# DM1097_MODULE_HSPEED.net
KiCad netlist of a schematic drawn in Altium Designer
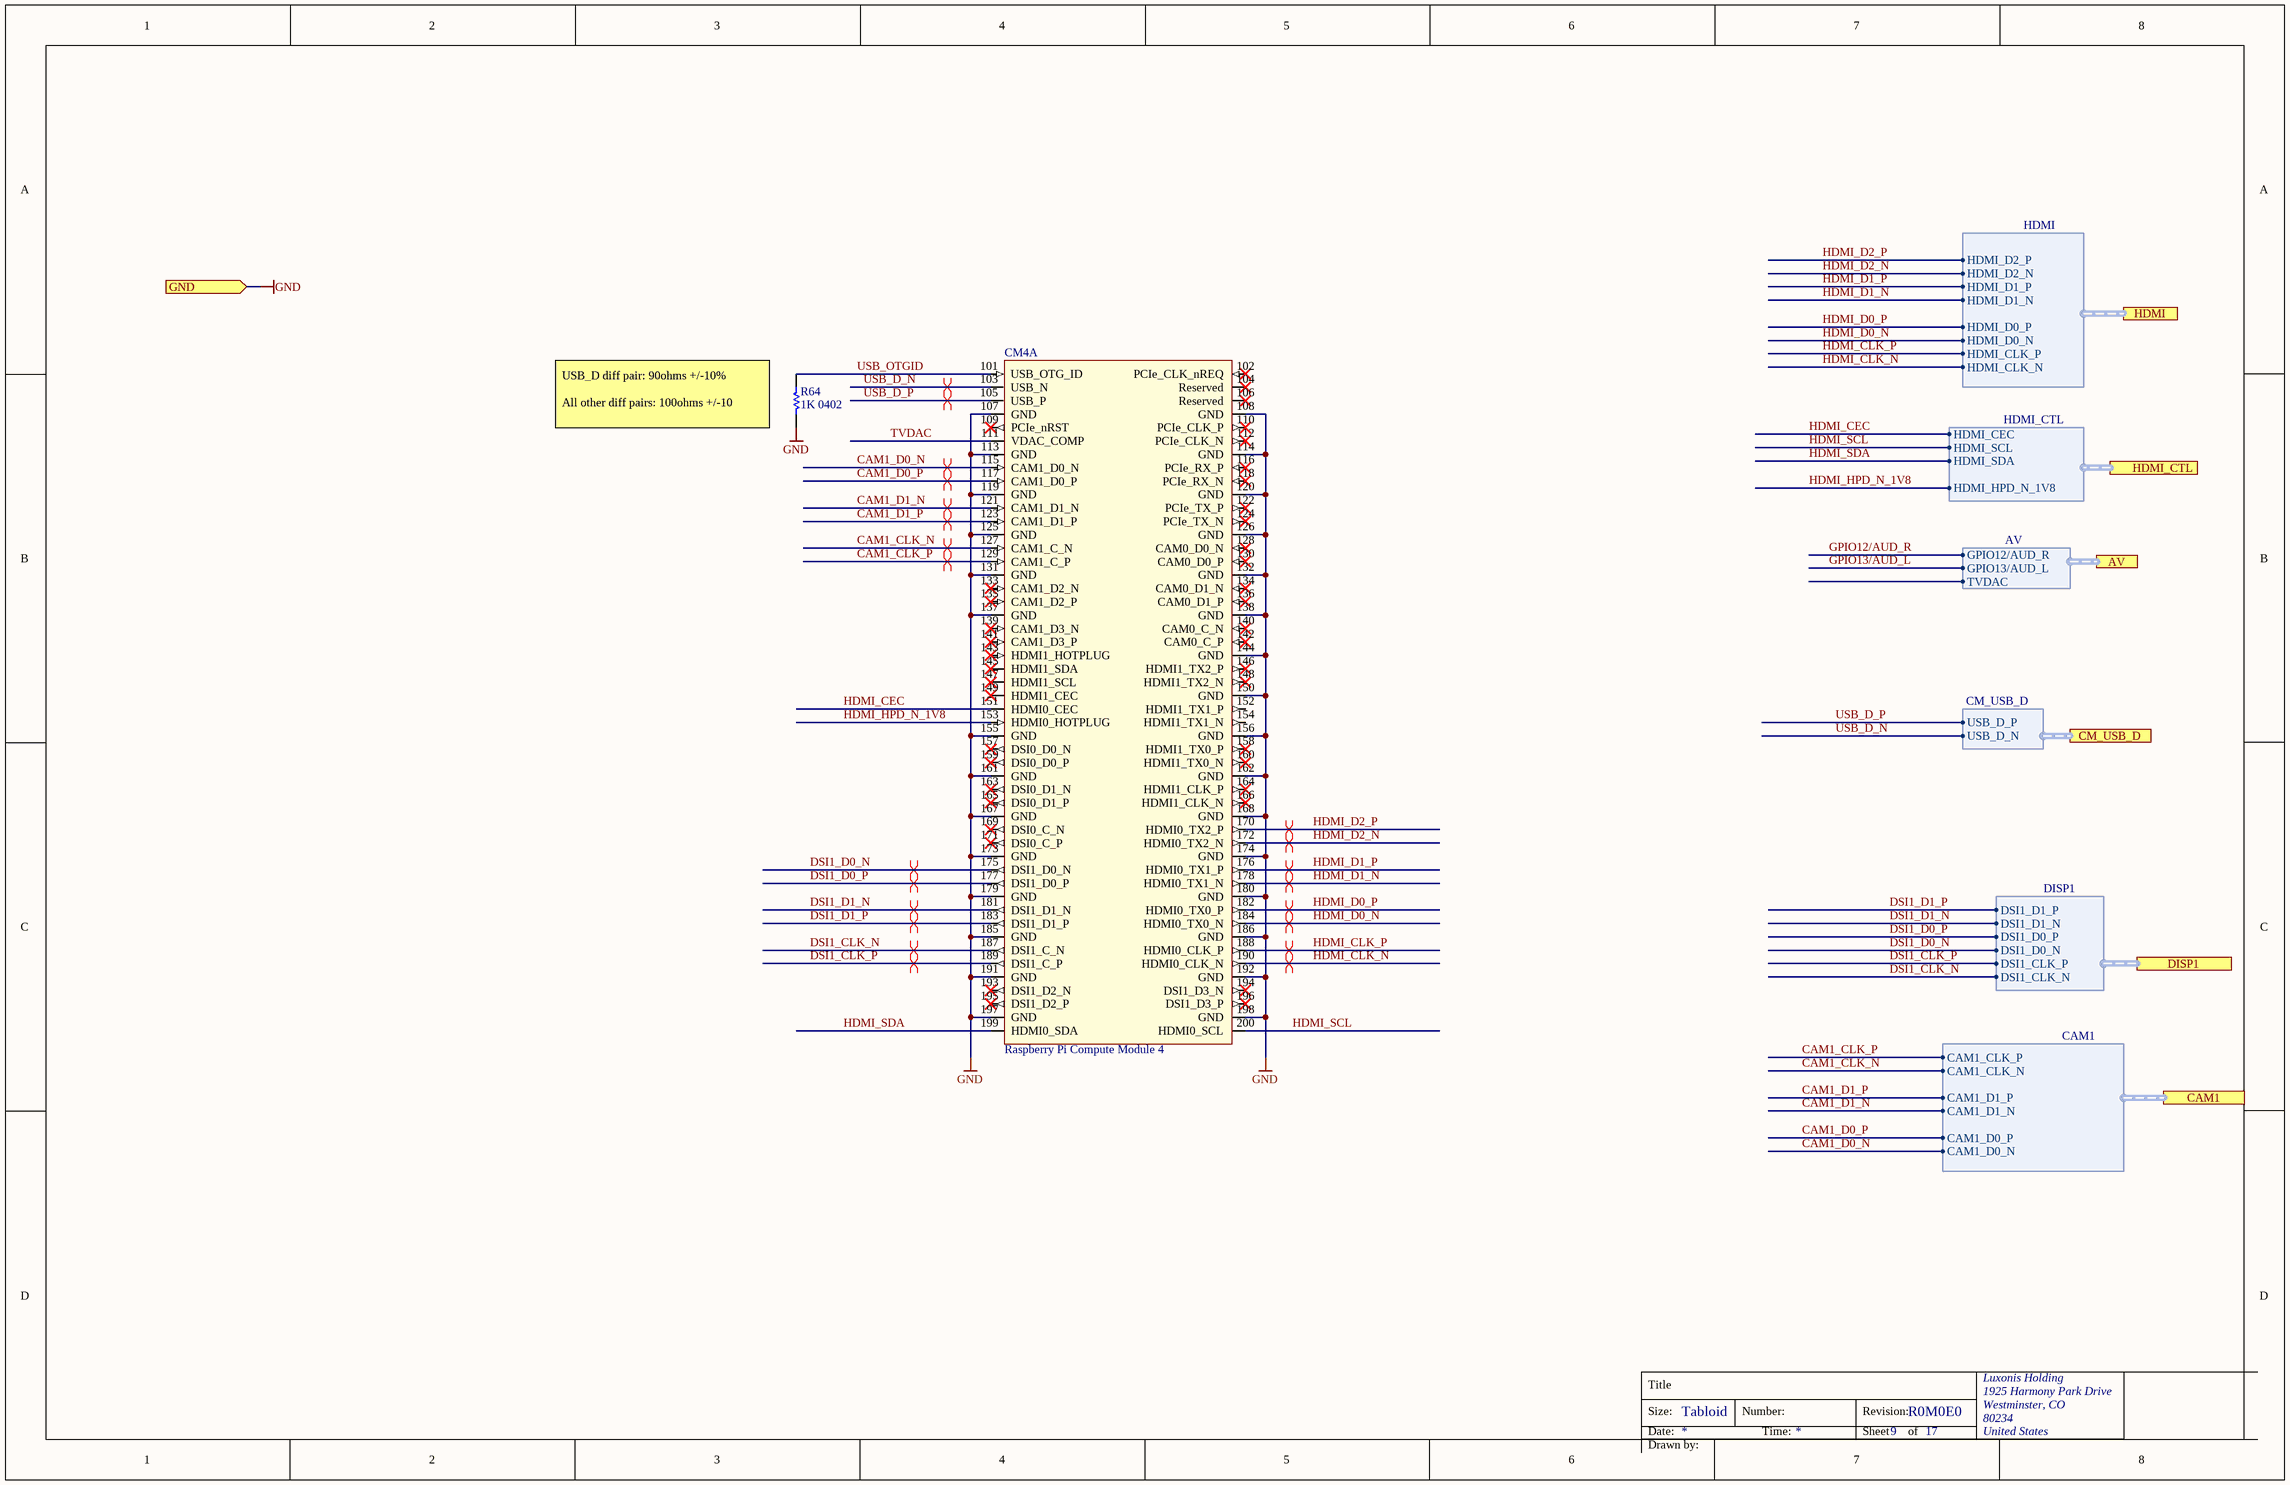
[diagram p0: DM1097_MODULE_HSPEED.SchDoc]

(export (version "E")
  (design (tool "Eeschema 10.0.6"))
  (components
    (comp (ref "CM4")
      (value "Raspberry Pi Compute Module 4")
      (footprint "CM4-DF40HC(3.0)-100DS-0.4v_3mm_1.5mm")
      (description "Raspberry Pi Compute Module 4\r\nTwo receptacle 100-pin connectors")
      (libsource (lib "DM1097_SchLib") (part "CM4"))
    )
    (comp (ref "R64")
      (value "1K 0402")
      (footprint "RES_Altium_Vault_Generic:RESC0402(1005)_N")
      (fields (field (name "TOLERANCE") "1%"))
      (libsource (lib "LuxonisMaster") (part "RC0402FR-071KL"))
    )
  )
  (nets
    (net (code "7") (name "/CAM1_CLK_N") (class "Default")
      (node (ref "CM4") (pin "127") (pinfunction "CAM1_C_N_127") (pintype "input"))
    )
    (net (code "8") (name "/CAM1_CLK_P") (class "Default")
      (node (ref "CM4") (pin "129") (pinfunction "CAM1_C_P_129") (pintype "input"))
    )
    (net (code "9") (name "/CAM1_D0_N") (class "Default")
      (node (ref "CM4") (pin "115") (pinfunction "CAM1_D0_N_115") (pintype "input"))
    )
    (net (code "10") (name "/CAM1_D0_P") (class "Default")
      (node (ref "CM4") (pin "117") (pinfunction "CAM1_D0_P_117") (pintype "input"))
    )
    (net (code "11") (name "/CAM1_D1_N") (class "Default")
      (node (ref "CM4") (pin "121") (pinfunction "CAM1_D1_N_121") (pintype "input"))
    )
    (net (code "12") (name "/CAM1_D1_P") (class "Default")
      (node (ref "CM4") (pin "123") (pinfunction "CAM1_D1_P_123") (pintype "input"))
    )
    (net (code "13") (name "/DSI1_CLK_N") (class "Default")
      (node (ref "CM4") (pin "187") (pinfunction "DSI1_C_N_187") (pintype "output"))
    )
    (net (code "14") (name "/DSI1_CLK_P") (class "Default")
      (node (ref "CM4") (pin "189") (pinfunction "DSI1_C_P_189") (pintype "output"))
    )
    (net (code "15") (name "/DSI1_D0_N") (class "Default")
      (node (ref "CM4") (pin "175") (pinfunction "DSI1_D0_N_175") (pintype "output"))
    )
    (net (code "16") (name "/DSI1_D0_P") (class "Default")
      (node (ref "CM4") (pin "177") (pinfunction "DSI1_D0_P_177") (pintype "output"))
    )
    (net (code "17") (name "/DSI1_D1_N") (class "Default")
      (node (ref "CM4") (pin "181") (pinfunction "DSI1_D1_N_181") (pintype "output"))
    )
    (net (code "18") (name "/DSI1_D1_P") (class "Default")
      (node (ref "CM4") (pin "183") (pinfunction "DSI1_D1_P_183") (pintype "output"))
    )
    (net (code "21") (name "/HDMI_CEC") (class "Default")
      (node (ref "CM4") (pin "151") (pinfunction "HDMI0_CEC_151") (pintype "open_collector"))
    )
    (net (code "22") (name "/HDMI_CLK_N") (class "Default")
      (node (ref "CM4") (pin "190") (pinfunction "HDMI0_CLK_N_190") (pintype "output"))
    )
    (net (code "23") (name "/HDMI_CLK_P") (class "Default")
      (node (ref "CM4") (pin "188") (pinfunction "HDMI0_CLK_P_188") (pintype "output"))
    )
    (net (code "24") (name "/HDMI_D0_N") (class "Default")
      (node (ref "CM4") (pin "184") (pinfunction "HDMI0_TX0_N_184") (pintype "output"))
    )
    (net (code "25") (name "/HDMI_D0_P") (class "Default")
      (node (ref "CM4") (pin "182") (pinfunction "HDMI0_TX0_P_182") (pintype "output"))
    )
    (net (code "26") (name "/HDMI_D1_N") (class "Default")
      (node (ref "CM4") (pin "178") (pinfunction "HDMI0_TX1_N_178") (pintype "output"))
    )
    (net (code "27") (name "/HDMI_D1_P") (class "Default")
      (node (ref "CM4") (pin "176") (pinfunction "HDMI0_TX1_P_176") (pintype "output"))
    )
    (net (code "28") (name "/HDMI_D2_N") (class "Default")
      (node (ref "CM4") (pin "172") (pinfunction "HDMI0_TX2_N_172") (pintype "output"))
    )
    (net (code "29") (name "/HDMI_D2_P") (class "Default")
      (node (ref "CM4") (pin "170") (pinfunction "HDMI0_TX2_P_170") (pintype "output"))
    )
    (net (code "30") (name "/HDMI_HPD_N_1V8") (class "Default")
      (node (ref "CM4") (pin "153") (pinfunction "HDMI0_HOTPLUG_153") (pintype "input"))
    )
    (net (code "31") (name "/HDMI_SCL") (class "Default")
      (node (ref "CM4") (pin "200") (pinfunction "HDMI0_SCL_200") (pintype "open_collector"))
    )
    (net (code "32") (name "/HDMI_SDA") (class "Default")
      (node (ref "CM4") (pin "199") (pinfunction "HDMI0_SDA_199") (pintype "bidirectional"))
    )
    (net (code "33") (name "/TVDAC") (class "Default")
      (node (ref "CM4") (pin "111") (pinfunction "VDAC_COMP_111") (pintype "passive"))
    )
    (net (code "34") (name "/USB_D_N") (class "Default")
      (node (ref "CM4") (pin "103") (pinfunction "USB_N_103") (pintype "passive"))
    )
    (net (code "35") (name "/USB_D_P") (class "Default")
      (node (ref "CM4") (pin "105") (pinfunction "USB_P_105") (pintype "passive"))
    )
    (net (code "36") (name "/USB_OTGID") (class "Default")
      (node (ref "CM4") (pin "101") (pinfunction "USB_OTG_ID_101") (pintype "input"))
      (node (ref "R64") (pin "2") (pinfunction "2_2") (pintype "passive"))
    )
    (net (code "43") (name "GND") (class "Default")
      (node (ref "CM4") (pin "107") (pinfunction "GND_107") (pintype "power_in"))
      (node (ref "CM4") (pin "108") (pinfunction "GND_108") (pintype "power_in"))
      (node (ref "CM4") (pin "113") (pinfunction "GND_113") (pintype "power_in"))
      (node (ref "CM4") (pin "114") (pinfunction "GND_114") (pintype "power_in"))
      (node (ref "CM4") (pin "119") (pinfunction "GND_119") (pintype "power_in"))
      (node (ref "CM4") (pin "120") (pinfunction "GND_120") (pintype "power_in"))
      (node (ref "CM4") (pin "125") (pinfunction "GND_125") (pintype "power_in"))
      (node (ref "CM4") (pin "126") (pinfunction "GND_126") (pintype "power_in"))
      (node (ref "CM4") (pin "131") (pinfunction "GND_131") (pintype "power_in"))
      (node (ref "CM4") (pin "132") (pinfunction "GND_132") (pintype "power_in"))
      (node (ref "CM4") (pin "137") (pinfunction "GND_137") (pintype "power_in"))
      (node (ref "CM4") (pin "138") (pinfunction "GND_138") (pintype "power_in"))
      (node (ref "CM4") (pin "144") (pinfunction "GND_144") (pintype "power_in"))
      (node (ref "CM4") (pin "150") (pinfunction "GND_150") (pintype "power_in"))
      (node (ref "CM4") (pin "155") (pinfunction "GND_155") (pintype "power_in"))
      (node (ref "CM4") (pin "156") (pinfunction "GND_156") (pintype "power_in"))
      (node (ref "CM4") (pin "161") (pinfunction "GND_161") (pintype "power_in"))
      (node (ref "CM4") (pin "162") (pinfunction "GND_162") (pintype "power_in"))
      (node (ref "CM4") (pin "167") (pinfunction "GND_167") (pintype "power_in"))
      (node (ref "CM4") (pin "168") (pinfunction "GND_168") (pintype "power_in"))
      (node (ref "CM4") (pin "173") (pinfunction "GND_173") (pintype "power_in"))
      (node (ref "CM4") (pin "174") (pinfunction "GND_174") (pintype "power_in"))
      (node (ref "CM4") (pin "179") (pinfunction "GND_179") (pintype "power_in"))
      (node (ref "CM4") (pin "180") (pinfunction "GND_180") (pintype "power_in"))
      (node (ref "CM4") (pin "185") (pinfunction "GND_185") (pintype "power_in"))
      (node (ref "CM4") (pin "186") (pinfunction "GND_186") (pintype "power_in"))
      (node (ref "CM4") (pin "191") (pinfunction "GND_191") (pintype "power_in"))
      (node (ref "CM4") (pin "192") (pinfunction "GND_192") (pintype "power_in"))
      (node (ref "CM4") (pin "197") (pinfunction "GND_197") (pintype "power_in"))
      (node (ref "CM4") (pin "198") (pinfunction "GND_198") (pintype "power_in"))
      (node (ref "R64") (pin "1") (pinfunction "1_1") (pintype "passive"))
    )
    (net (code "44") (name "unconnected-(CM4A-CAM0_C_N-Pad140)") (class "Default")
      (node (ref "CM4") (pin "140") (pinfunction "CAM0_C_N_140") (pintype "input+no_connect"))
    )
    (net (code "45") (name "unconnected-(CM4A-CAM0_C_P-Pad142)") (class "Default")
      (node (ref "CM4") (pin "142") (pinfunction "CAM0_C_P_142") (pintype "input+no_connect"))
    )
    (net (code "46") (name "unconnected-(CM4A-CAM0_D0_N-Pad128)") (class "Default")
      (node (ref "CM4") (pin "128") (pinfunction "CAM0_D0_N_128") (pintype "input+no_connect"))
    )
    (net (code "47") (name "unconnected-(CM4A-CAM0_D0_P-Pad130)") (class "Default")
      (node (ref "CM4") (pin "130") (pinfunction "CAM0_D0_P_130") (pintype "input+no_connect"))
    )
    (net (code "48") (name "unconnected-(CM4A-CAM0_D1_N-Pad134)") (class "Default")
      (node (ref "CM4") (pin "134") (pinfunction "CAM0_D1_N_134") (pintype "input+no_connect"))
    )
    (net (code "49") (name "unconnected-(CM4A-CAM0_D1_P-Pad136)") (class "Default")
      (node (ref "CM4") (pin "136") (pinfunction "CAM0_D1_P_136") (pintype "input+no_connect"))
    )
    (net (code "50") (name "unconnected-(CM4A-CAM1_D2_N-Pad133)") (class "Default")
      (node (ref "CM4") (pin "133") (pinfunction "CAM1_D2_N_133") (pintype "input+no_connect"))
    )
    (net (code "51") (name "unconnected-(CM4A-CAM1_D2_P-Pad135)") (class "Default")
      (node (ref "CM4") (pin "135") (pinfunction "CAM1_D2_P_135") (pintype "input+no_connect"))
    )
    (net (code "52") (name "unconnected-(CM4A-CAM1_D3_N-Pad139)") (class "Default")
      (node (ref "CM4") (pin "139") (pinfunction "CAM1_D3_N_139") (pintype "input+no_connect"))
    )
    (net (code "53") (name "unconnected-(CM4A-CAM1_D3_P-Pad141)") (class "Default")
      (node (ref "CM4") (pin "141") (pinfunction "CAM1_D3_P_141") (pintype "input+no_connect"))
    )
    (net (code "54") (name "unconnected-(CM4A-DSI0_C_N-Pad169)") (class "Default")
      (node (ref "CM4") (pin "169") (pinfunction "DSI0_C_N_169") (pintype "output+no_connect"))
    )
    (net (code "55") (name "unconnected-(CM4A-DSI0_C_P-Pad171)") (class "Default")
      (node (ref "CM4") (pin "171") (pinfunction "DSI0_C_P_171") (pintype "output+no_connect"))
    )
    (net (code "56") (name "unconnected-(CM4A-DSI0_D0_N-Pad157)") (class "Default")
      (node (ref "CM4") (pin "157") (pinfunction "DSI0_D0_N_157") (pintype "output+no_connect"))
    )
    (net (code "57") (name "unconnected-(CM4A-DSI0_D0_P-Pad159)") (class "Default")
      (node (ref "CM4") (pin "159") (pinfunction "DSI0_D0_P_159") (pintype "output+no_connect"))
    )
    (net (code "58") (name "unconnected-(CM4A-DSI0_D1_N-Pad163)") (class "Default")
      (node (ref "CM4") (pin "163") (pinfunction "DSI0_D1_N_163") (pintype "output+no_connect"))
    )
    (net (code "59") (name "unconnected-(CM4A-DSI0_D1_P-Pad165)") (class "Default")
      (node (ref "CM4") (pin "165") (pinfunction "DSI0_D1_P_165") (pintype "output+no_connect"))
    )
    (net (code "60") (name "unconnected-(CM4A-DSI1_D2_N-Pad193)") (class "Default")
      (node (ref "CM4") (pin "193") (pinfunction "DSI1_D2_N_193") (pintype "output+no_connect"))
    )
    (net (code "61") (name "unconnected-(CM4A-DSI1_D2_P-Pad195)") (class "Default")
      (node (ref "CM4") (pin "195") (pinfunction "DSI1_D2_P_195") (pintype "output+no_connect"))
    )
    (net (code "62") (name "unconnected-(CM4A-DSI1_D3_N-Pad194)") (class "Default")
      (node (ref "CM4") (pin "194") (pinfunction "DSI1_D3_N_194") (pintype "output+no_connect"))
    )
    (net (code "63") (name "unconnected-(CM4A-DSI1_D3_P-Pad196)") (class "Default")
      (node (ref "CM4") (pin "196") (pinfunction "DSI1_D3_P_196") (pintype "output+no_connect"))
    )
    (net (code "64") (name "unconnected-(CM4A-HDMI1_CEC-Pad149)") (class "Default")
      (node (ref "CM4") (pin "149") (pinfunction "HDMI1_CEC_149") (pintype "open_collector+no_connect"))
    )
    (net (code "65") (name "unconnected-(CM4A-HDMI1_CLK_N-Pad166)") (class "Default")
      (node (ref "CM4") (pin "166") (pinfunction "HDMI1_CLK_N_166") (pintype "output+no_connect"))
    )
    (net (code "66") (name "unconnected-(CM4A-HDMI1_CLK_P-Pad164)") (class "Default")
      (node (ref "CM4") (pin "164") (pinfunction "HDMI1_CLK_P_164") (pintype "output+no_connect"))
    )
    (net (code "67") (name "unconnected-(CM4A-HDMI1_HOTPLUG-Pad143)") (class "Default")
      (node (ref "CM4") (pin "143") (pinfunction "HDMI1_HOTPLUG_143") (pintype "input+no_connect"))
    )
    (net (code "68") (name "unconnected-(CM4A-HDMI1_SCL-Pad147)") (class "Default")
      (node (ref "CM4") (pin "147") (pinfunction "HDMI1_SCL_147") (pintype "open_collector+no_connect"))
    )
    (net (code "69") (name "unconnected-(CM4A-HDMI1_SDA-Pad145)") (class "Default")
      (node (ref "CM4") (pin "145") (pinfunction "HDMI1_SDA_145") (pintype "bidirectional+no_connect"))
    )
    (net (code "70") (name "unconnected-(CM4A-HDMI1_TX0_N-Pad160)") (class "Default")
      (node (ref "CM4") (pin "160") (pinfunction "HDMI1_TX0_N_160") (pintype "output+no_connect"))
    )
    (net (code "71") (name "unconnected-(CM4A-HDMI1_TX0_P-Pad158)") (class "Default")
      (node (ref "CM4") (pin "158") (pinfunction "HDMI1_TX0_P_158") (pintype "output+no_connect"))
    )
    (net (code "72") (name "unconnected-(CM4A-HDMI1_TX1_N-Pad154)") (class "Default")
      (node (ref "CM4") (pin "154") (pinfunction "HDMI1_TX1_N_154") (pintype "output"))
    )
    (net (code "73") (name "unconnected-(CM4A-HDMI1_TX1_P-Pad152)") (class "Default")
      (node (ref "CM4") (pin "152") (pinfunction "HDMI1_TX1_P_152") (pintype "output"))
    )
    (net (code "74") (name "unconnected-(CM4A-HDMI1_TX2_N-Pad148)") (class "Default")
      (node (ref "CM4") (pin "148") (pinfunction "HDMI1_TX2_N_148") (pintype "output+no_connect"))
    )
    (net (code "75") (name "unconnected-(CM4A-HDMI1_TX2_P-Pad146)") (class "Default")
      (node (ref "CM4") (pin "146") (pinfunction "HDMI1_TX2_P_146") (pintype "output+no_connect"))
    )
    (net (code "76") (name "unconnected-(CM4A-PCIe_CLK_N-Pad112)") (class "Default")
      (node (ref "CM4") (pin "112") (pinfunction "PCIe_CLK_N_112") (pintype "output+no_connect"))
    )
    (net (code "77") (name "unconnected-(CM4A-PCIe_CLK_P-Pad110)") (class "Default")
      (node (ref "CM4") (pin "110") (pinfunction "PCIe_CLK_P_110") (pintype "output+no_connect"))
    )
    (net (code "78") (name "unconnected-(CM4A-PCIe_CLK_nREQ-Pad102)") (class "Default")
      (node (ref "CM4") (pin "102") (pinfunction "PCIe_CLK_nREQ_102") (pintype "input+no_connect"))
    )
    (net (code "79") (name "unconnected-(CM4A-PCIe_RX_N-Pad118)") (class "Default")
      (node (ref "CM4") (pin "118") (pinfunction "PCIe_RX_N_118") (pintype "input+no_connect"))
    )
    (net (code "80") (name "unconnected-(CM4A-PCIe_RX_P-Pad116)") (class "Default")
      (node (ref "CM4") (pin "116") (pinfunction "PCIe_RX_P_116") (pintype "input+no_connect"))
    )
    (net (code "81") (name "unconnected-(CM4A-PCIe_TX_N-Pad124)") (class "Default")
      (node (ref "CM4") (pin "124") (pinfunction "PCIe_TX_N_124") (pintype "output+no_connect"))
    )
    (net (code "82") (name "unconnected-(CM4A-PCIe_TX_P-Pad122)") (class "Default")
      (node (ref "CM4") (pin "122") (pinfunction "PCIe_TX_P_122") (pintype "output+no_connect"))
    )
    (net (code "83") (name "unconnected-(CM4A-PCIe_nRST-Pad109)") (class "Default")
      (node (ref "CM4") (pin "109") (pinfunction "PCIe_nRST_109") (pintype "output+no_connect"))
    )
    (net (code "84") (name "unconnected-(CM4A-Reserved-Pad104)") (class "Default")
      (node (ref "CM4") (pin "104") (pinfunction "Reserved_104") (pintype "passive+no_connect"))
    )
    (net (code "85") (name "unconnected-(CM4A-Reserved-Pad106)") (class "Default")
      (node (ref "CM4") (pin "106") (pinfunction "Reserved_106") (pintype "passive+no_connect"))
    )
  )
)
